# v2.net
KiCad netlist of a schematic drawn in EAGLE
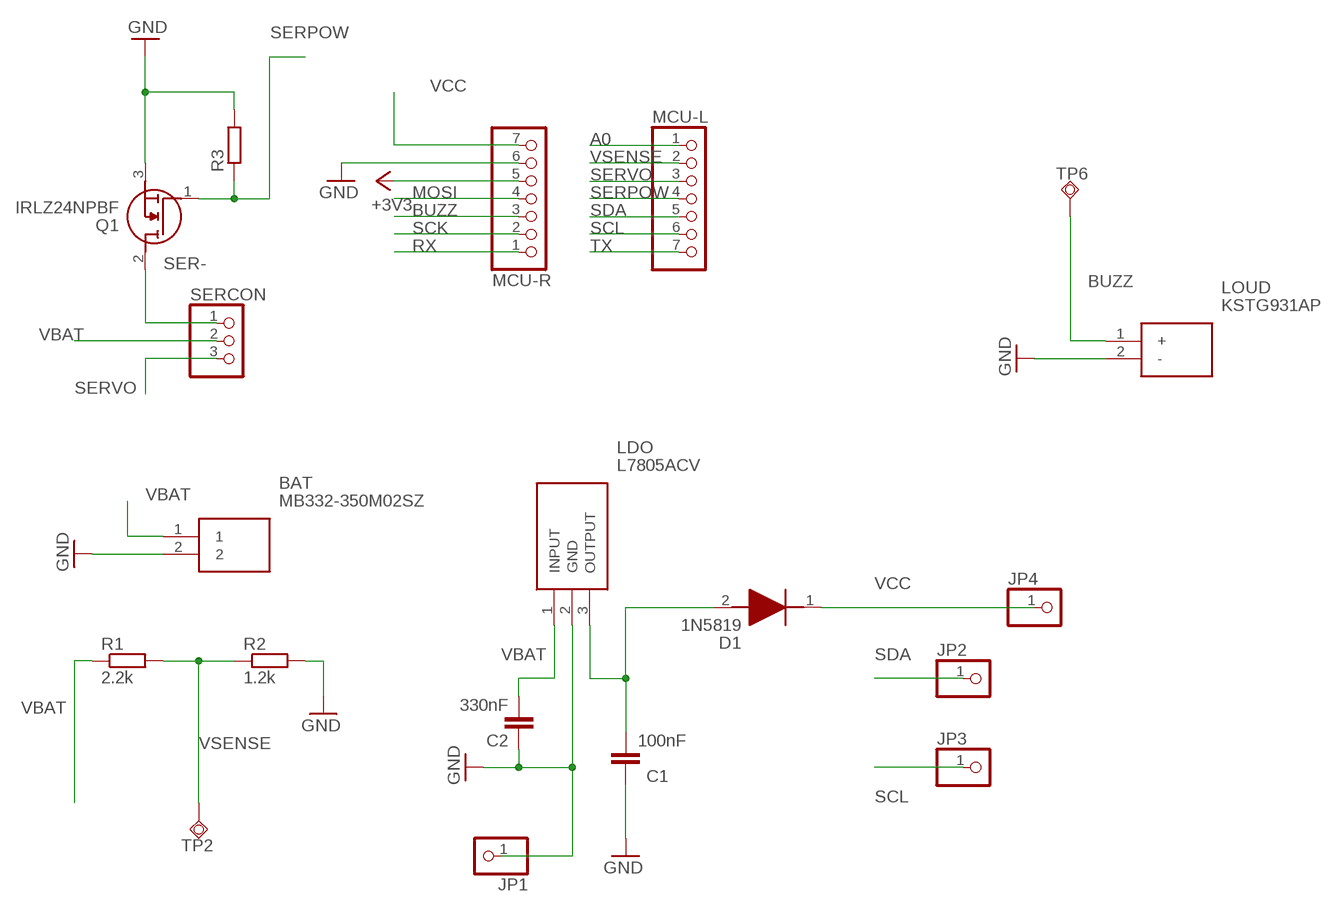
[diagram p0: schematic, sheet 1]

(export (version "E")
  (design (tool "Eeschema 10.0.6"))
  (components
    (comp (ref "BAT")
      (value "MB332-350M02SZ")
      (footprint "eagle-import:MB332350M02SZ")
      (fields (field (name "RS_PART_NUMBER") "7901149"))
      (libsource (lib "eagle-import") (part "MB332-350M02SZ"))
    )
    (comp (ref "C1")
      (value "100nF")
      (footprint "eagle-import:C025-024X044")
      (libsource (lib "eagle-import") (part "C-EU025-024X044"))
    )
    (comp (ref "C2")
      (value "330nF")
      (footprint "eagle-import:C025-024X044")
      (libsource (lib "eagle-import") (part "C-EU025-024X044"))
    )
    (comp (ref "D1")
      (value "1N5819")
      (footprint "eagle-import:DIOAD1414W86L464D238")
      (fields (field (name "RS_PART_NUMBER") "4864460P"))
      (libsource (lib "eagle-import") (part "1N5819"))
    )
    (comp (ref "JP1")
      (value "PINHD-1X1")
      (footprint "eagle-import:1X01")
      (libsource (lib "eagle-import") (part "PINHD-1X1"))
    )
    (comp (ref "JP2")
      (value "PINHD-1X1")
      (footprint "eagle-import:1X01")
      (libsource (lib "eagle-import") (part "PINHD-1X1"))
    )
    (comp (ref "JP3")
      (value "PINHD-1X1")
      (footprint "eagle-import:1X01")
      (libsource (lib "eagle-import") (part "PINHD-1X1"))
    )
    (comp (ref "JP4")
      (value "PINHD-1X1")
      (footprint "eagle-import:1X01")
      (libsource (lib "eagle-import") (part "PINHD-1X1"))
    )
    (comp (ref "LDO")
      (value "L7805ACV")
      (footprint "eagle-import:TO255P460X1020X2008-3P")
      (fields (field (name "RS_PART_NUMBER") "2988508P"))
      (libsource (lib "eagle-import") (part "L7805ACV"))
    )
    (comp (ref "LOUD")
      (value "KSTG931AP")
      (footprint "eagle-import:CAPPRD400W70D900H500")
      (libsource (lib "eagle-import") (part "KSTG931AP"))
    )
    (comp (ref "MCU-L")
      (value "HEADER-1X7")
      (footprint "eagle-import:1X07_OVAL")
      (libsource (lib "eagle-import") (part "HEADER-1X7"))
    )
    (comp (ref "MCU-R")
      (value "HEADER-1X7")
      (footprint "eagle-import:1X07_OVAL")
      (libsource (lib "eagle-import") (part "HEADER-1X7"))
    )
    (comp (ref "Q1")
      (value "IRLZ24NPBF")
      (footprint "eagle-import:TO254P469X1042X1967-3P")
      (fields (field (name "RS_PART_NUMBER") "5411231P"))
      (libsource (lib "eagle-import") (part "IRLZ24NPBF"))
    )
    (comp (ref "R1")
      (value "2.2k")
      (footprint "eagle-import:0204V")
      (libsource (lib "eagle-import") (part "R-EU_0204/2V"))
    )
    (comp (ref "R2")
      (value "1.2k")
      (footprint "eagle-import:0204V")
      (libsource (lib "eagle-import") (part "R-EU_0204/2V"))
    )
    (comp (ref "R3")
      (value "R-EU_0204/2V")
      (footprint "eagle-import:0204V")
      (libsource (lib "eagle-import") (part "R-EU_0204/2V"))
    )
    (comp (ref "SERCON")
      (value "PINHD-1X3")
      (footprint "eagle-import:1X03")
      (libsource (lib "eagle-import") (part "PINHD-1X3"))
    )
    (comp (ref "TP2")
      (value "TPSQB2,54")
      (footprint "eagle-import:B2,54")
      (libsource (lib "eagle-import") (part "TPSQB2,54"))
    )
    (comp (ref "TP6")
      (value "TPSQB2,54")
      (footprint "eagle-import:B2,54")
      (libsource (lib "eagle-import") (part "TPSQB2,54"))
    )
  )
  (nets
    (net (code "1") (name "+3V3") (class "Default")
      (node (ref "MCU-R") (pin "5") (pinfunction "5_5") (pintype "passive"))
    )
    (net (code "2") (name "/A0") (class "Default")
      (node (ref "MCU-L") (pin "1") (pinfunction "1_1") (pintype "passive"))
    )
    (net (code "3") (name "/BUZZ") (class "Default")
      (node (ref "LOUD") (pin "1") (pinfunction "+_1") (pintype "bidirectional"))
      (node (ref "MCU-R") (pin "3") (pinfunction "3_3") (pintype "passive"))
      (node (ref "TP6") (pin "TP") (pinfunction "TP_TP") (pintype "input"))
    )
    (net (code "4") (name "/MOSI") (class "Default")
      (node (ref "MCU-R") (pin "4") (pinfunction "4_4") (pintype "passive"))
    )
    (net (code "5") (name "/RX") (class "Default")
      (node (ref "MCU-R") (pin "1") (pinfunction "1_1") (pintype "passive"))
    )
    (net (code "6") (name "/SCK") (class "Default")
      (node (ref "MCU-R") (pin "2") (pinfunction "2_2") (pintype "passive"))
    )
    (net (code "7") (name "/SCL") (class "Default")
      (node (ref "JP3") (pin "1") (pinfunction "1_1") (pintype "passive"))
      (node (ref "MCU-L") (pin "6") (pinfunction "6_6") (pintype "passive"))
    )
    (net (code "8") (name "/SDA") (class "Default")
      (node (ref "JP2") (pin "1") (pinfunction "1_1") (pintype "passive"))
      (node (ref "MCU-L") (pin "5") (pinfunction "5_5") (pintype "passive"))
    )
    (net (code "9") (name "/SER-") (class "Default")
      (node (ref "Q1") (pin "2") (pinfunction "D_2") (pintype "bidirectional"))
      (node (ref "SERCON") (pin "1") (pinfunction "1_1") (pintype "passive"))
    )
    (net (code "10") (name "/SERPOW") (class "Default")
      (node (ref "MCU-L") (pin "4") (pinfunction "4_4") (pintype "passive"))
      (node (ref "Q1") (pin "1") (pinfunction "G_1") (pintype "bidirectional"))
      (node (ref "R3") (pin "1") (pinfunction "1_1") (pintype "passive"))
    )
    (net (code "11") (name "/SERVO") (class "Default")
      (node (ref "MCU-L") (pin "3") (pinfunction "3_3") (pintype "passive"))
      (node (ref "SERCON") (pin "3") (pinfunction "3_3") (pintype "passive"))
    )
    (net (code "12") (name "/TX") (class "Default")
      (node (ref "MCU-L") (pin "7") (pinfunction "7_7") (pintype "passive"))
    )
    (net (code "13") (name "/VBAT") (class "Default")
      (node (ref "BAT") (pin "1") (pinfunction "1_1") (pintype "bidirectional"))
      (node (ref "C2") (pin "2") (pinfunction "2_2") (pintype "passive"))
      (node (ref "LDO") (pin "1") (pinfunction "INPUT_1") (pintype "bidirectional"))
      (node (ref "R1") (pin "1") (pinfunction "1_1") (pintype "passive"))
      (node (ref "SERCON") (pin "2") (pinfunction "2_2") (pintype "passive"))
    )
    (net (code "14") (name "/VCC") (class "Default")
      (node (ref "D1") (pin "1") (pinfunction "K_1") (pintype "bidirectional"))
      (node (ref "JP4") (pin "1") (pinfunction "1_1") (pintype "passive"))
      (node (ref "MCU-R") (pin "7") (pinfunction "7_7") (pintype "passive"))
    )
    (net (code "15") (name "/VSENSE") (class "Default")
      (node (ref "MCU-L") (pin "2") (pinfunction "2_2") (pintype "passive"))
      (node (ref "R1") (pin "2") (pinfunction "2_2") (pintype "passive"))
      (node (ref "R2") (pin "1") (pinfunction "1_1") (pintype "passive"))
      (node (ref "TP2") (pin "TP") (pinfunction "TP_TP") (pintype "input"))
    )
    (net (code "16") (name "GND") (class "Default")
      (node (ref "BAT") (pin "2") (pinfunction "2_2") (pintype "bidirectional"))
      (node (ref "C1") (pin "1") (pinfunction "1_1") (pintype "passive"))
      (node (ref "C2") (pin "1") (pinfunction "1_1") (pintype "passive"))
      (node (ref "JP1") (pin "1") (pinfunction "1_1") (pintype "passive"))
      (node (ref "LDO") (pin "2") (pinfunction "GND_2") (pintype "bidirectional"))
      (node (ref "LOUD") (pin "2") (pinfunction "-_2") (pintype "bidirectional"))
      (node (ref "MCU-R") (pin "6") (pinfunction "6_6") (pintype "passive"))
      (node (ref "Q1") (pin "3") (pinfunction "S_3") (pintype "bidirectional"))
      (node (ref "R2") (pin "2") (pinfunction "2_2") (pintype "passive"))
      (node (ref "R3") (pin "2") (pinfunction "2_2") (pintype "passive"))
    )
    (net (code "17") (name "Net-(D1-A)") (class "Default")
      (node (ref "C1") (pin "2") (pinfunction "2_2") (pintype "passive"))
      (node (ref "D1") (pin "2") (pinfunction "A_2") (pintype "bidirectional"))
      (node (ref "LDO") (pin "3") (pinfunction "OUTPUT_3") (pintype "bidirectional"))
    )
  )
)
